# ne555dimmer.net
KiCad netlist of a schematic drawn in Altium Designer
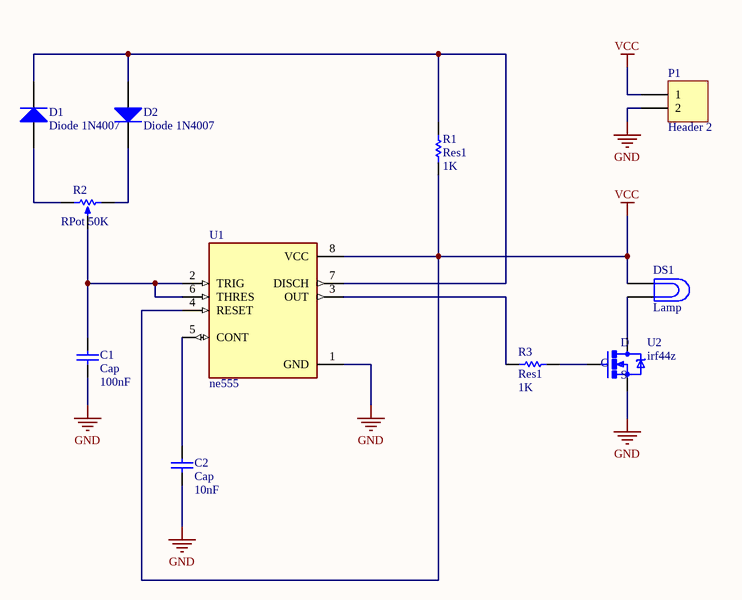
[diagram p0: ne555dimmer.SchDoc]

(export (version "E")
  (design (tool "Eeschema 10.0.6"))
  (components
    (comp (ref "C1")
      (value "Cap")
      (footprint "RAD-0.3")
      (description "Capacitor")
      (fields (field (name "ALTIUM_VALUE") "100nF") (field (name "PUBLISHER") "Altium Limited"))
      (libsource (lib "Miscellaneous Devices") (part "Cap"))
    )
    (comp (ref "C2")
      (value "Cap")
      (footprint "RAD-0.3")
      (description "Capacitor")
      (fields (field (name "ALTIUM_VALUE") "10nF") (field (name "PUBLISHER") "Altium Limited"))
      (libsource (lib "Miscellaneous Devices") (part "Cap"))
    )
    (comp (ref "D1")
      (value "Diode 1N4007")
      (footprint "DO-41")
      (description "1 Amp General Purpose Rectifier")
      (fields (field (name "PUBLISHER") "Altium Limited"))
      (libsource (lib "Miscellaneous Devices") (part "Diode 1N4007"))
    )
    (comp (ref "D2")
      (value "Diode 1N4007")
      (footprint "DO-41")
      (description "1 Amp General Purpose Rectifier")
      (fields (field (name "PUBLISHER") "Altium Limited"))
      (libsource (lib "Miscellaneous Devices") (part "Diode 1N4007"))
    )
    (comp (ref "DS1")
      (value "Lamp")
      (footprint "PIN2")
      (description "Incandescent Bulb")
      (fields (field (name "PUBLISHER") "Altium Limited"))
      (libsource (lib "Miscellaneous Devices") (part "Lamp"))
    )
    (comp (ref "P1")
      (value "Header 2")
      (footprint "HDR1X2")
      (description "Header, 2-Pin")
      (fields (field (name "PUBLISHER") "Altium Limited"))
      (libsource (lib "Miscellaneous Connectors") (part "Header 2"))
    )
    (comp (ref "R1")
      (value "Res1")
      (footprint "AXIAL-0.3")
      (description "Resistor")
      (fields (field (name "ALTIUM_VALUE") "1K") (field (name "PUBLISHER") "Altium Limited"))
      (libsource (lib "Miscellaneous Devices") (part "Res1"))
    )
    (comp (ref "R2")
      (value "RPot")
      (footprint "VR5")
      (description "Potentiometer")
      (fields (field (name "ALTIUM_VALUE") "50K") (field (name "PUBLISHER") "Altium Limited"))
      (libsource (lib "Miscellaneous Devices") (part "RPot"))
    )
    (comp (ref "R3")
      (value "Res1")
      (footprint "AXIAL-0.3")
      (description "Resistor")
      (fields (field (name "ALTIUM_VALUE") "1K") (field (name "PUBLISHER") "Altium Limited"))
      (libsource (lib "Miscellaneous Devices") (part "Res1"))
    )
    (comp (ref "U1") (value "ne555") (footprint "ne555") (libsource (lib "ne555dimmer") (part "ne555")))
    (comp (ref "U2") (value "irf44z") (footprint "ırfz44") (libsource (lib "ne555dimmer") (part "irf44z")))
  )
  (nets
    (net (code "1") (name "GND") (class "Default")
      (node (ref "C1") (pin "1") (pinfunction "1_1") (pintype "passive"))
      (node (ref "C2") (pin "1") (pinfunction "1_1") (pintype "passive"))
      (node (ref "P1") (pin "2") (pinfunction "2_2") (pintype "passive"))
      (node (ref "U1") (pin "1") (pinfunction "GND_1") (pintype "power_in"))
      (node (ref "U2") (pin "3") (pinfunction "S_3") (pintype "passive"))
    )
    (net (code "2") (name "Net-(D1-A)") (class "Default")
      (node (ref "D1") (pin "1") (pinfunction "A_1") (pintype "passive"))
      (node (ref "R2") (pin "1") (pinfunction "TOP_1") (pintype "passive"))
    )
    (net (code "3") (name "Net-(D1-K)") (class "Default")
      (node (ref "D1") (pin "2") (pinfunction "K_2") (pintype "passive"))
      (node (ref "D2") (pin "1") (pinfunction "A_1") (pintype "passive"))
      (node (ref "R1") (pin "2") (pinfunction "2_2") (pintype "passive"))
      (node (ref "U1") (pin "7") (pinfunction "DISCH_7") (pintype "output"))
    )
    (net (code "4") (name "Net-(D2-K)") (class "Default")
      (node (ref "D2") (pin "2") (pinfunction "K_2") (pintype "passive"))
      (node (ref "R2") (pin "2") (pinfunction "BOT_2") (pintype "passive"))
    )
    (net (code "5") (name "Net-(R2-TAP)") (class "Default")
      (node (ref "C1") (pin "2") (pinfunction "2_2") (pintype "passive"))
      (node (ref "R2") (pin "3") (pinfunction "TAP_3") (pintype "passive"))
      (node (ref "U1") (pin "2") (pinfunction "TRIG_2") (pintype "input"))
      (node (ref "U1") (pin "6") (pinfunction "THRES_6") (pintype "input"))
    )
    (net (code "6") (name "Net-(U1-CONT)") (class "Default")
      (node (ref "C2") (pin "2") (pinfunction "2_2") (pintype "passive"))
      (node (ref "U1") (pin "5") (pinfunction "CONT_5") (pintype "bidirectional"))
    )
    (net (code "7") (name "Net-(U1-OUT)") (class "Default")
      (node (ref "R3") (pin "1") (pinfunction "1_1") (pintype "passive"))
      (node (ref "U1") (pin "3") (pinfunction "OUT_3") (pintype "output"))
    )
    (net (code "8") (name "Net-(U2-D)") (class "Default")
      (node (ref "DS1") (pin "2") (pinfunction "2_2") (pintype "passive"))
      (node (ref "U2") (pin "2") (pinfunction "D_2") (pintype "passive"))
    )
    (net (code "9") (name "Net-(U2-G)") (class "Default")
      (node (ref "R3") (pin "2") (pinfunction "2_2") (pintype "passive"))
      (node (ref "U2") (pin "1") (pinfunction "G_1") (pintype "passive"))
    )
    (net (code "10") (name "VCC") (class "Default")
      (node (ref "DS1") (pin "1") (pinfunction "1_1") (pintype "passive"))
      (node (ref "P1") (pin "1") (pinfunction "1_1") (pintype "passive"))
      (node (ref "R1") (pin "1") (pinfunction "1_1") (pintype "passive"))
      (node (ref "U1") (pin "4") (pinfunction "RESET_4") (pintype "input"))
      (node (ref "U1") (pin "8") (pinfunction "VCC_8") (pintype "power_in"))
    )
  )
)
